# Williamson88.net
KiCad netlist of a schematic drawn in EAGLE
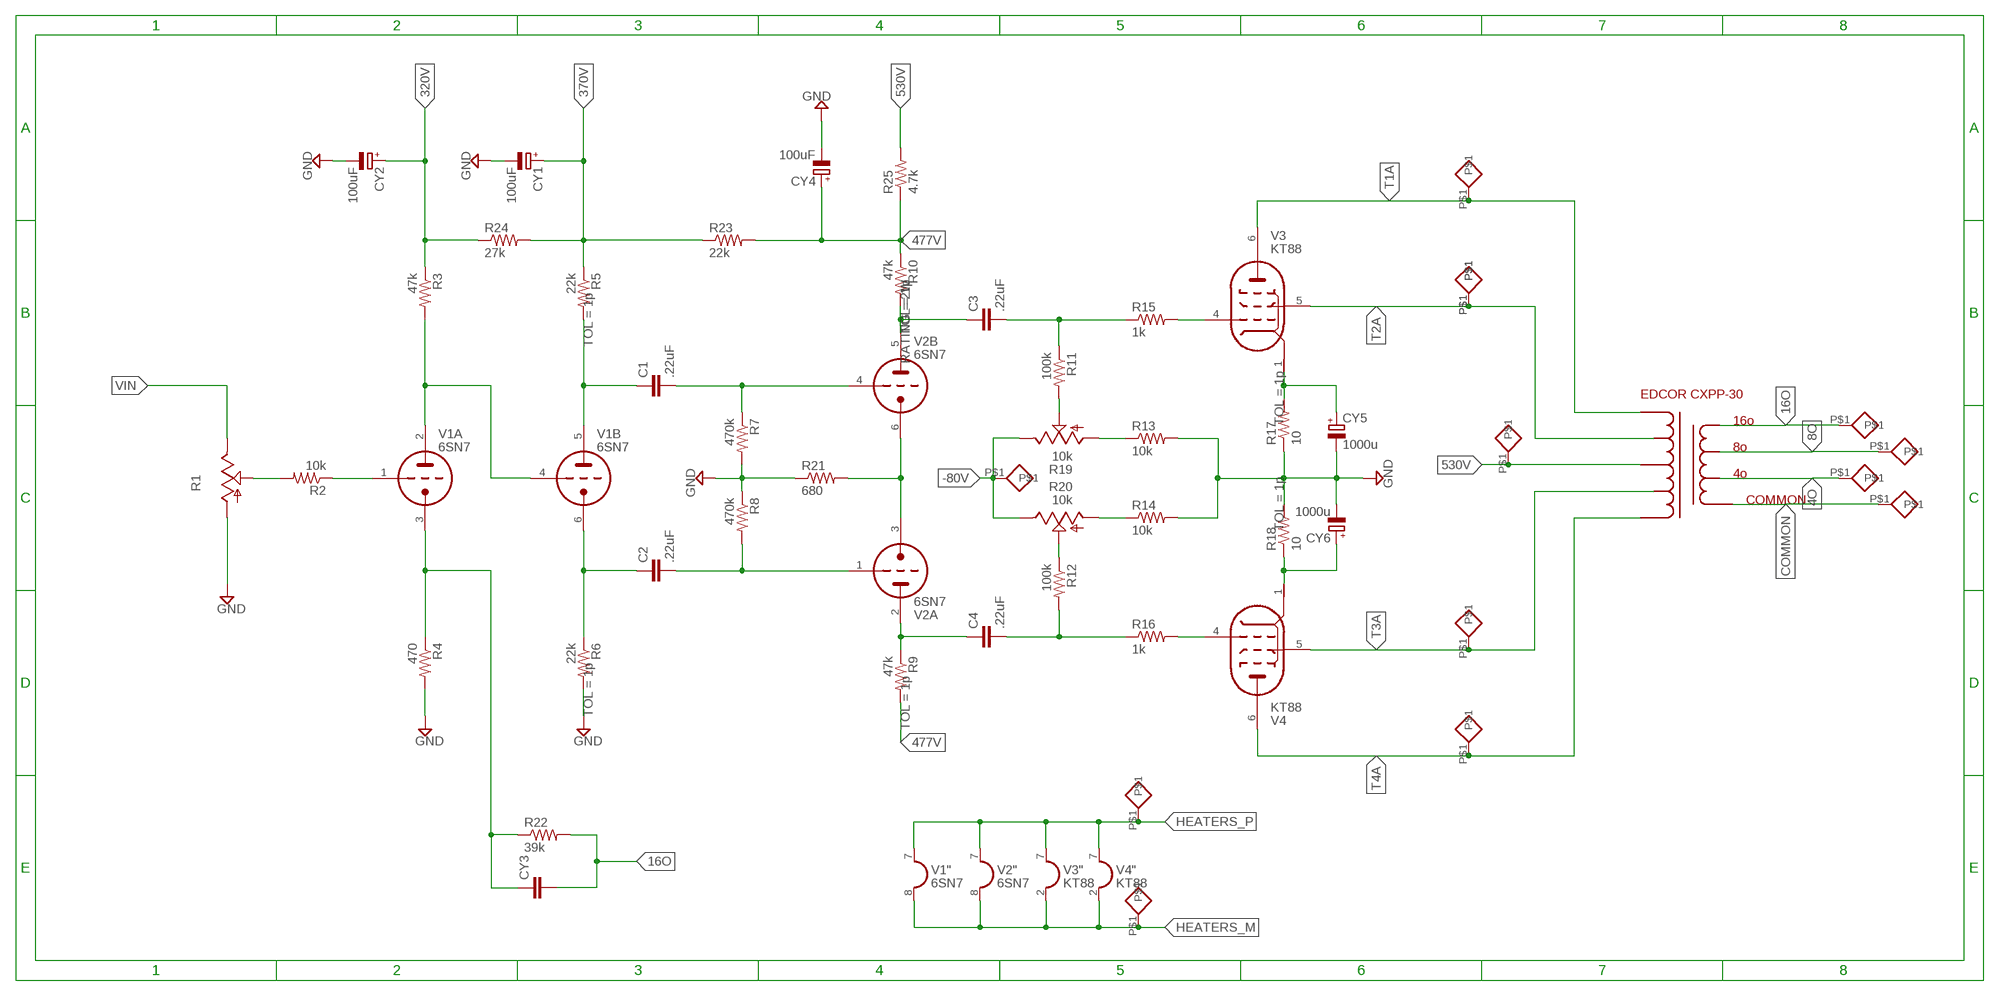
[diagram p0: schematic, sheet 1]

(export (version "E")
  (design (tool "Eeschema 10.0.6"))
  (components
    (comp (ref "C1")
      (value ".22uF")
      (footprint "eagle-import:C225-062X268")
      (fields (field (name "MPN") "150224J630LE"))
      (libsource (lib "eagle-import") (part "C-EU225-062X268"))
    )
    (comp (ref "C2")
      (value ".22uF")
      (footprint "eagle-import:C225-062X268")
      (fields (field (name "MPN") "150224J630LE"))
      (libsource (lib "eagle-import") (part "C-EU225-062X268"))
    )
    (comp (ref "C3")
      (value ".22uF")
      (footprint "eagle-import:C225-062X268")
      (fields (field (name "MPN") "150224J630LE"))
      (libsource (lib "eagle-import") (part "C-EU225-062X268"))
    )
    (comp (ref "C4")
      (value ".22uF")
      (footprint "eagle-import:C225-062X268")
      (fields (field (name "MPN") "150224J630LE"))
      (libsource (lib "eagle-import") (part "C-EU225-062X268"))
    )
    (comp (ref "CY1")
      (value "100uF")
      (footprint "eagle-import:E7,5-18")
      (libsource (lib "eagle-import") (part "CPOL-EUE7.5-18"))
    )
    (comp (ref "CY2")
      (value "100uF")
      (footprint "eagle-import:E7,5-18")
      (libsource (lib "eagle-import") (part "CPOL-EUE7.5-18"))
    )
    (comp (ref "CY3")
      (value "CYYC10B5")
      (footprint "eagle-import:YC10B5")
      (libsource (lib "eagle-import") (part "CYYC10B5"))
    )
    (comp (ref "CY4")
      (value "100uF")
      (footprint "eagle-import:E7,5-18")
      (libsource (lib "eagle-import") (part "CPOL-EUE7.5-18"))
    )
    (comp (ref "CY5")
      (value "1000u")
      (footprint "eagle-import:E7,5-18")
      (libsource (lib "eagle-import") (part "CPOL-EUE7.5-18"))
    )
    (comp (ref "CY6")
      (value "1000u")
      (footprint "eagle-import:E7,5-18")
      (libsource (lib "eagle-import") (part "CPOL-EUE7.5-18"))
    )
    (comp (ref "R1")
      (value "TRIM_US-B25P")
      (footprint "eagle-import:B25P")
      (libsource (lib "eagle-import") (part "TRIM_US-B25P"))
    )
    (comp (ref "R2")
      (value "10k")
      (footprint "eagle-import:0309_10")
      (libsource (lib "eagle-import") (part "R-US_0309/10"))
    )
    (comp (ref "R3")
      (value "47k")
      (footprint "eagle-import:0309_10")
      (libsource (lib "eagle-import") (part "R-US_0309/10"))
    )
    (comp (ref "R4")
      (value "470")
      (footprint "eagle-import:0309_10")
      (libsource (lib "eagle-import") (part "R-US_0309/10"))
    )
    (comp (ref "R5")
      (value "22k")
      (footprint "eagle-import:0309_10")
      (fields (field (name "TOL") "1p"))
      (libsource (lib "eagle-import") (part "R-US_0309/10"))
    )
    (comp (ref "R6")
      (value "22k")
      (footprint "eagle-import:0309_10")
      (fields (field (name "TOL") "1p"))
      (libsource (lib "eagle-import") (part "R-US_0309/10"))
    )
    (comp (ref "R7")
      (value "470k")
      (footprint "eagle-import:0309_10")
      (libsource (lib "eagle-import") (part "R-US_0309/10"))
    )
    (comp (ref "R8")
      (value "470k")
      (footprint "eagle-import:0309_10")
      (libsource (lib "eagle-import") (part "R-US_0309/10"))
    )
    (comp (ref "R9")
      (value "47k")
      (footprint "eagle-import:0309_10")
      (fields (field (name "TOL") "1p"))
      (libsource (lib "eagle-import") (part "R-US_0309/10"))
    )
    (comp (ref "R10")
      (value "47k")
      (footprint "eagle-import:0309_10")
      (fields (field (name "RATING") "2W") (field (name "TOL") "1p"))
      (libsource (lib "eagle-import") (part "R-US_0309/10"))
    )
    (comp (ref "R11")
      (value "100k")
      (footprint "eagle-import:0309_10")
      (libsource (lib "eagle-import") (part "R-US_0309/10"))
    )
    (comp (ref "R12")
      (value "100k")
      (footprint "eagle-import:0309_10")
      (libsource (lib "eagle-import") (part "R-US_0309/10"))
    )
    (comp (ref "R13")
      (value "10k")
      (footprint "eagle-import:0309_10")
      (libsource (lib "eagle-import") (part "R-US_0309/10"))
    )
    (comp (ref "R14")
      (value "10k")
      (footprint "eagle-import:0309_10")
      (libsource (lib "eagle-import") (part "R-US_0309/10"))
    )
    (comp (ref "R15")
      (value "1k")
      (footprint "eagle-import:0309_10")
      (libsource (lib "eagle-import") (part "R-US_0309/10"))
    )
    (comp (ref "R16")
      (value "1k")
      (footprint "eagle-import:0309_10")
      (libsource (lib "eagle-import") (part "R-US_0309/10"))
    )
    (comp (ref "R17")
      (value "10")
      (footprint "eagle-import:0309_10")
      (fields (field (name "TOL") "1p"))
      (libsource (lib "eagle-import") (part "R-US_0309/10"))
    )
    (comp (ref "R18")
      (value "10")
      (footprint "eagle-import:0309_10")
      (fields (field (name "TOL") "1p"))
      (libsource (lib "eagle-import") (part "R-US_0309/10"))
    )
    (comp (ref "R19")
      (value "10k")
      (footprint "eagle-import:B25P")
      (libsource (lib "eagle-import") (part "TRIM_US-B25P"))
    )
    (comp (ref "R20")
      (value "10k")
      (footprint "eagle-import:B25P")
      (libsource (lib "eagle-import") (part "TRIM_US-B25P"))
    )
    (comp (ref "R21")
      (value "680")
      (footprint "eagle-import:0309_10")
      (libsource (lib "eagle-import") (part "R-US_0309/10"))
    )
    (comp (ref "R22")
      (value "39k")
      (footprint "eagle-import:0309_10")
      (libsource (lib "eagle-import") (part "R-US_0309/10"))
    )
    (comp (ref "R23")
      (value "22k")
      (footprint "eagle-import:0309_10")
      (libsource (lib "eagle-import") (part "R-US_0309/10"))
    )
    (comp (ref "R24")
      (value "27k")
      (footprint "eagle-import:0309_10")
      (libsource (lib "eagle-import") (part "R-US_0309/10"))
    )
    (comp (ref "R25")
      (value "4.7k")
      (footprint "eagle-import:0309_10")
      (libsource (lib "eagle-import") (part "R-US_0309/10"))
    )
    (comp (ref "U$1")
      (value "CXPP30")
      (footprint "eagle-import:CXPP30")
      (libsource (lib "eagle-import") (part "CXPP30"))
    )
    (comp (ref "U$2")
      (value "W_CONN")
      (footprint "eagle-import:WIRE_T")
      (libsource (lib "eagle-import") (part "W_CONN"))
    )
    (comp (ref "U$3")
      (value "W_CONN")
      (footprint "eagle-import:WIRE_T")
      (libsource (lib "eagle-import") (part "W_CONN"))
    )
    (comp (ref "U$4")
      (value "W_CONN")
      (footprint "eagle-import:WIRE_T")
      (libsource (lib "eagle-import") (part "W_CONN"))
    )
    (comp (ref "U$5")
      (value "W_CONN")
      (footprint "eagle-import:WIRE_T")
      (libsource (lib "eagle-import") (part "W_CONN"))
    )
    (comp (ref "U$6")
      (value "W_CONN")
      (footprint "eagle-import:WIRE_T")
      (libsource (lib "eagle-import") (part "W_CONN"))
    )
    (comp (ref "U$7")
      (value "W_CONN")
      (footprint "eagle-import:WIRE_T")
      (libsource (lib "eagle-import") (part "W_CONN"))
    )
    (comp (ref "U$8")
      (value "W_CONN")
      (footprint "eagle-import:WIRE_T")
      (libsource (lib "eagle-import") (part "W_CONN"))
    )
    (comp (ref "U$9")
      (value "W_CONN")
      (footprint "eagle-import:WIRE_T")
      (libsource (lib "eagle-import") (part "W_CONN"))
    )
    (comp (ref "U$10")
      (value "W_CONN")
      (footprint "eagle-import:WIRE_T")
      (libsource (lib "eagle-import") (part "W_CONN"))
    )
    (comp (ref "U$14")
      (value "W_CONN")
      (footprint "eagle-import:WIRE_T")
      (libsource (lib "eagle-import") (part "W_CONN"))
    )
    (comp (ref "U$15")
      (value "W_CONN")
      (footprint "eagle-import:WIRE_T")
      (libsource (lib "eagle-import") (part "W_CONN"))
    )
    (comp (ref "U$17")
      (value "W_CONN")
      (footprint "eagle-import:WIRE_T")
      (libsource (lib "eagle-import") (part "W_CONN"))
    )
    (comp (ref "U$18")
      (value "W_CONN")
      (footprint "eagle-import:WIRE_T")
      (libsource (lib "eagle-import") (part "W_CONN"))
    )
    (comp (ref "V1")
      (value "6SN7")
      (footprint "eagle-import:OKTAL")
      (libsource (lib "eagle-import") (part "6SN7GT-P"))
    )
    (comp (ref "V2")
      (value "6SN7")
      (footprint "eagle-import:OKTAL")
      (libsource (lib "eagle-import") (part "6SN7GT-P"))
    )
    (comp (ref "V3")
      (value "KT88")
      (footprint "eagle-import:OKTAL")
      (libsource (lib "eagle-import") (part "KT88-P"))
    )
    (comp (ref "V4")
      (value "KT88")
      (footprint "eagle-import:OKTAL")
      (libsource (lib "eagle-import") (part "KT88-P"))
    )
  )
  (nets
    (net (code "1") (name "-80V") (class "Default")
      (node (ref "R19") (pin "E") (pinfunction "E_E") (pintype "passive"))
      (node (ref "R20") (pin "E") (pinfunction "E_E") (pintype "passive"))
      (node (ref "U$10") (pin "P$1") (pinfunction "P$1_P$1") (pintype "bidirectional"))
    )
    (net (code "2") (name "4O") (class "Default")
      (node (ref "U$8") (pin "P$1") (pinfunction "P$1_P$1") (pintype "bidirectional"))
    )
    (net (code "3") (name "8O") (class "Default")
      (node (ref "U$7") (pin "P$1") (pinfunction "P$1_P$1") (pintype "bidirectional"))
    )
    (net (code "4") (name "16O") (class "Default")
      (node (ref "CY3") (pin "2") (pinfunction "2_2") (pintype "passive"))
      (node (ref "R22") (pin "2") (pinfunction "2_2") (pintype "passive"))
      (node (ref "U$6") (pin "P$1") (pinfunction "P$1_P$1") (pintype "bidirectional"))
    )
    (net (code "5") (name "320V") (class "Default")
      (node (ref "CY2") (pin "+") (pinfunction "+_+") (pintype "passive"))
      (node (ref "R24") (pin "1") (pinfunction "1_1") (pintype "passive"))
      (node (ref "R3") (pin "1") (pinfunction "1_1") (pintype "passive"))
    )
    (net (code "6") (name "370V") (class "Default")
      (node (ref "CY1") (pin "+") (pinfunction "+_+") (pintype "passive"))
      (node (ref "R23") (pin "1") (pinfunction "1_1") (pintype "passive"))
      (node (ref "R24") (pin "2") (pinfunction "2_2") (pintype "passive"))
      (node (ref "R5") (pin "1") (pinfunction "1_1") (pintype "passive"))
    )
    (net (code "7") (name "477V") (class "Default")
      (node (ref "CY4") (pin "+") (pinfunction "+_+") (pintype "passive"))
      (node (ref "R10") (pin "1") (pinfunction "1_1") (pintype "passive"))
      (node (ref "R23") (pin "2") (pinfunction "2_2") (pintype "passive"))
      (node (ref "R25") (pin "1") (pinfunction "1_1") (pintype "passive"))
      (node (ref "R9") (pin "2") (pinfunction "2_2") (pintype "passive"))
    )
    (net (code "8") (name "530V") (class "Default")
      (node (ref "R25") (pin "2") (pinfunction "2_2") (pintype "passive"))
      (node (ref "U$18") (pin "P$1") (pinfunction "P$1_P$1") (pintype "bidirectional"))
    )
    (net (code "9") (name "COMMON") (class "Default")
      (node (ref "U$9") (pin "P$1") (pinfunction "P$1_P$1") (pintype "bidirectional"))
    )
    (net (code "10") (name "GND") (class "Default")
      (node (ref "CY1") (pin "-") (pinfunction "-_-") (pintype "passive"))
      (node (ref "CY2") (pin "-") (pinfunction "-_-") (pintype "passive"))
      (node (ref "CY4") (pin "-") (pinfunction "-_-") (pintype "passive"))
      (node (ref "CY5") (pin "-") (pinfunction "-_-") (pintype "passive"))
      (node (ref "CY6") (pin "-") (pinfunction "-_-") (pintype "passive"))
      (node (ref "R1") (pin "A") (pinfunction "A_A") (pintype "passive"))
      (node (ref "R13") (pin "2") (pinfunction "2_2") (pintype "passive"))
      (node (ref "R14") (pin "2") (pinfunction "2_2") (pintype "passive"))
      (node (ref "R17") (pin "1") (pinfunction "1_1") (pintype "passive"))
      (node (ref "R18") (pin "2") (pinfunction "2_2") (pintype "passive"))
      (node (ref "R21") (pin "1") (pinfunction "1_1") (pintype "passive"))
      (node (ref "R4") (pin "2") (pinfunction "2_2") (pintype "passive"))
      (node (ref "R6") (pin "2") (pinfunction "2_2") (pintype "passive"))
      (node (ref "R7") (pin "2") (pinfunction "2_2") (pintype "passive"))
      (node (ref "R8") (pin "1") (pinfunction "1_1") (pintype "passive"))
    )
    (net (code "11") (name "HEATERS_M") (class "Default")
      (node (ref "U$15") (pin "P$1") (pinfunction "P$1_P$1") (pintype "bidirectional"))
      (node (ref "V1") (pin "8") (pinfunction "H2_8") (pintype "passive"))
      (node (ref "V2") (pin "8") (pinfunction "H2_8") (pintype "passive"))
      (node (ref "V3") (pin "2") (pinfunction "H2_2") (pintype "passive"))
      (node (ref "V4") (pin "2") (pinfunction "H2_2") (pintype "passive"))
    )
    (net (code "12") (name "HEATERS_P") (class "Default")
      (node (ref "U$14") (pin "P$1") (pinfunction "P$1_P$1") (pintype "bidirectional"))
      (node (ref "V1") (pin "7") (pinfunction "H1_7") (pintype "passive"))
      (node (ref "V2") (pin "7") (pinfunction "H1_7") (pintype "passive"))
      (node (ref "V3") (pin "7") (pinfunction "H1_7") (pintype "passive"))
      (node (ref "V4") (pin "7") (pinfunction "H1_7") (pintype "passive"))
    )
    (net (code "13") (name "Net-(C3-Pad2)") (class "Default")
      (node (ref "C3") (pin "2") (pinfunction "2_2") (pintype "passive"))
      (node (ref "R11") (pin "1") (pinfunction "1_1") (pintype "passive"))
      (node (ref "R15") (pin "1") (pinfunction "1_1") (pintype "passive"))
    )
    (net (code "14") (name "Net-(C4-Pad2)") (class "Default")
      (node (ref "C4") (pin "2") (pinfunction "2_2") (pintype "passive"))
      (node (ref "R12") (pin "2") (pinfunction "2_2") (pintype "passive"))
      (node (ref "R16") (pin "1") (pinfunction "1_1") (pintype "passive"))
    )
    (net (code "15") (name "Net-(R1-PadS)") (class "Default")
      (node (ref "R1") (pin "S") (pinfunction "S_S") (pintype "passive"))
      (node (ref "R2") (pin "2") (pinfunction "2_2") (pintype "passive"))
    )
    (net (code "16") (name "Net-(R11-Pad2)") (class "Default")
      (node (ref "R11") (pin "2") (pinfunction "2_2") (pintype "passive"))
      (node (ref "R19") (pin "S") (pinfunction "S_S") (pintype "passive"))
    )
    (net (code "17") (name "Net-(R12-Pad1)") (class "Default")
      (node (ref "R12") (pin "1") (pinfunction "1_1") (pintype "passive"))
      (node (ref "R20") (pin "S") (pinfunction "S_S") (pintype "passive"))
    )
    (net (code "18") (name "Net-(R13-Pad1)") (class "Default")
      (node (ref "R13") (pin "1") (pinfunction "1_1") (pintype "passive"))
      (node (ref "R19") (pin "A") (pinfunction "A_A") (pintype "passive"))
    )
    (net (code "19") (name "Net-(R14-Pad1)") (class "Default")
      (node (ref "R14") (pin "1") (pinfunction "1_1") (pintype "passive"))
      (node (ref "R20") (pin "A") (pinfunction "A_A") (pintype "passive"))
    )
    (net (code "20") (name "Net-(V1B-TA)") (class "Default")
      (node (ref "R3") (pin "2") (pinfunction "2_2") (pintype "passive"))
      (node (ref "V1") (pin "2") (pinfunction "TA_2") (pintype "passive"))
      (node (ref "V1") (pin "4") (pinfunction "TG_4") (pintype "passive"))
    )
    (net (code "21") (name "Net-(V1B-TG)") (class "Default")
      (node (ref "R2") (pin "1") (pinfunction "1_1") (pintype "passive"))
      (node (ref "V1") (pin "1") (pinfunction "TG_1") (pintype "passive"))
    )
    (net (code "22") (name "Net-(V1B-TK)") (class "Default")
      (node (ref "CY3") (pin "1") (pinfunction "1_1") (pintype "passive"))
      (node (ref "R22") (pin "1") (pinfunction "1_1") (pintype "passive"))
      (node (ref "R4") (pin "1") (pinfunction "1_1") (pintype "passive"))
      (node (ref "V1") (pin "3") (pinfunction "TK_3") (pintype "passive"))
    )
    (net (code "23") (name "Net-(V1C-TA)") (class "Default")
      (node (ref "C1") (pin "1") (pinfunction "1_1") (pintype "passive"))
      (node (ref "R5") (pin "2") (pinfunction "2_2") (pintype "passive"))
      (node (ref "V1") (pin "5") (pinfunction "TA_5") (pintype "passive"))
    )
    (net (code "24") (name "Net-(V1C-TK)") (class "Default")
      (node (ref "C2") (pin "1") (pinfunction "1_1") (pintype "passive"))
      (node (ref "R6") (pin "1") (pinfunction "1_1") (pintype "passive"))
      (node (ref "V1") (pin "6") (pinfunction "TK_6") (pintype "passive"))
    )
    (net (code "25") (name "Net-(V2B-TA)") (class "Default")
      (node (ref "C4") (pin "1") (pinfunction "1_1") (pintype "passive"))
      (node (ref "R9") (pin "1") (pinfunction "1_1") (pintype "passive"))
      (node (ref "V2") (pin "2") (pinfunction "TA_2") (pintype "passive"))
    )
    (net (code "26") (name "Net-(V2B-TG)") (class "Default")
      (node (ref "C2") (pin "2") (pinfunction "2_2") (pintype "passive"))
      (node (ref "R8") (pin "2") (pinfunction "2_2") (pintype "passive"))
      (node (ref "V2") (pin "1") (pinfunction "TG_1") (pintype "passive"))
    )
    (net (code "27") (name "Net-(V2B-TK)") (class "Default")
      (node (ref "R21") (pin "2") (pinfunction "2_2") (pintype "passive"))
      (node (ref "V2") (pin "3") (pinfunction "TK_3") (pintype "passive"))
      (node (ref "V2") (pin "6") (pinfunction "TK_6") (pintype "passive"))
    )
    (net (code "28") (name "Net-(V2C-TA)") (class "Default")
      (node (ref "C3") (pin "1") (pinfunction "1_1") (pintype "passive"))
      (node (ref "R10") (pin "2") (pinfunction "2_2") (pintype "passive"))
      (node (ref "V2") (pin "5") (pinfunction "TA_5") (pintype "passive"))
    )
    (net (code "29") (name "Net-(V2C-TG)") (class "Default")
      (node (ref "C1") (pin "2") (pinfunction "2_2") (pintype "passive"))
      (node (ref "R7") (pin "1") (pinfunction "1_1") (pintype "passive"))
      (node (ref "V2") (pin "4") (pinfunction "TG_4") (pintype "passive"))
    )
    (net (code "30") (name "Net-(V3B-PG)") (class "Default")
      (node (ref "R15") (pin "2") (pinfunction "2_2") (pintype "passive"))
      (node (ref "V3") (pin "4") (pinfunction "PG_4") (pintype "passive"))
    )
    (net (code "31") (name "Net-(V3B-PK)") (class "Default")
      (node (ref "CY5") (pin "+") (pinfunction "+_+") (pintype "passive"))
      (node (ref "R17") (pin "2") (pinfunction "2_2") (pintype "passive"))
      (node (ref "V3") (pin "1") (pinfunction "PK_1") (pintype "passive"))
    )
    (net (code "32") (name "Net-(V4B-PG)") (class "Default")
      (node (ref "R16") (pin "2") (pinfunction "2_2") (pintype "passive"))
      (node (ref "V4") (pin "4") (pinfunction "PG_4") (pintype "passive"))
    )
    (net (code "33") (name "Net-(V4B-PK)") (class "Default")
      (node (ref "CY6") (pin "+") (pinfunction "+_+") (pintype "passive"))
      (node (ref "R18") (pin "1") (pinfunction "1_1") (pintype "passive"))
      (node (ref "V4") (pin "1") (pinfunction "PK_1") (pintype "passive"))
    )
    (net (code "34") (name "T1A") (class "Default")
      (node (ref "U$2") (pin "P$1") (pinfunction "P$1_P$1") (pintype "bidirectional"))
      (node (ref "V3") (pin "6") (pinfunction "PA_6") (pintype "passive"))
    )
    (net (code "35") (name "T2A") (class "Default")
      (node (ref "U$17") (pin "P$1") (pinfunction "P$1_P$1") (pintype "bidirectional"))
      (node (ref "U$3") (pin "P$1") (pinfunction "P$1_P$1") (pintype "bidirectional"))
      (node (ref "V3") (pin "5") (pinfunction "PSG_5") (pintype "passive"))
    )
    (net (code "36") (name "T3A") (class "Default")
      (node (ref "U$4") (pin "P$1") (pinfunction "P$1_P$1") (pintype "bidirectional"))
      (node (ref "V4") (pin "5") (pinfunction "PSG_5") (pintype "passive"))
    )
    (net (code "37") (name "T4A") (class "Default")
      (node (ref "U$5") (pin "P$1") (pinfunction "P$1_P$1") (pintype "bidirectional"))
      (node (ref "V4") (pin "6") (pinfunction "PA_6") (pintype "passive"))
    )
    (net (code "38") (name "VIN") (class "Default")
      (node (ref "R1") (pin "E") (pinfunction "E_E") (pintype "passive"))
    )
  )
)
